# DC075B_DECOUPLING.net
KiCad netlist of a schematic drawn in Altium Designer
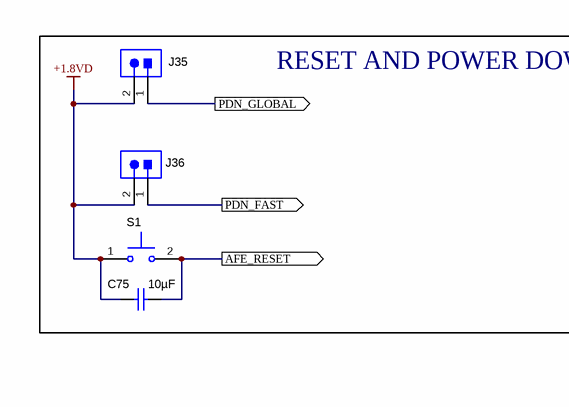
[diagram p0: DC075B_DECOUPLING.SchDoc, top left]
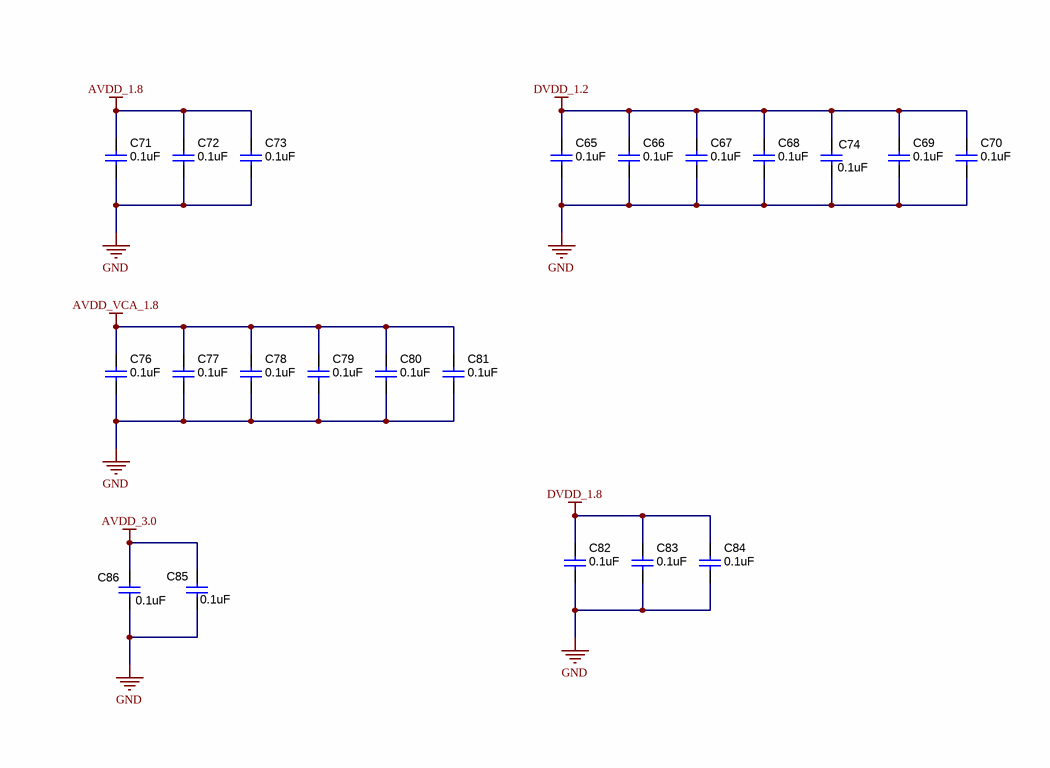
[diagram p1: DC075B_DECOUPLING.SchDoc, top right]
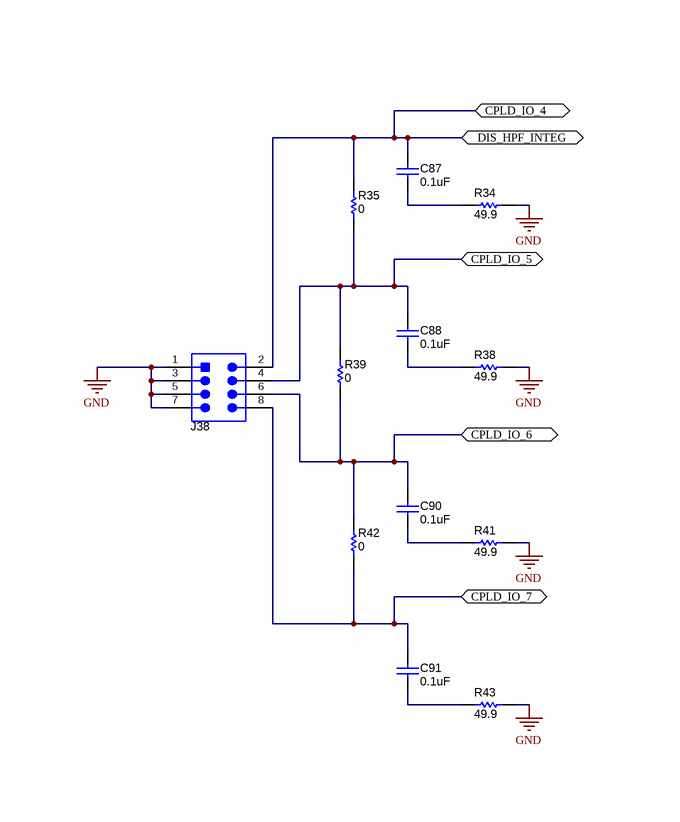
[diagram p2: DC075B_DECOUPLING.SchDoc, bottom left]
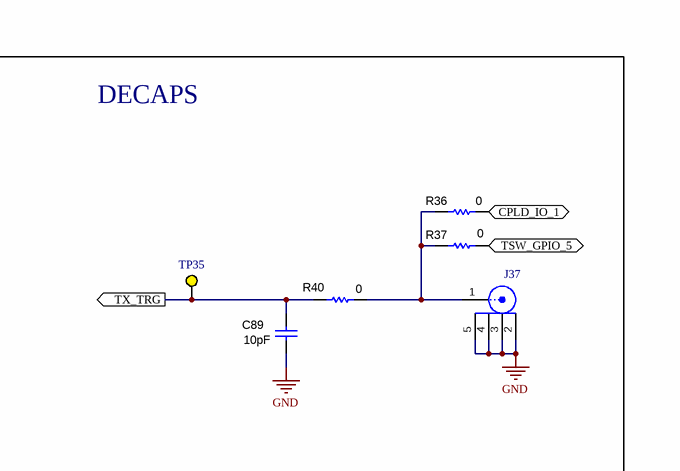
[diagram p3: DC075B_DECOUPLING.SchDoc, bottom right]

(export (version "E")
  (design (tool "Eeschema 10.0.6"))
  (components
    (comp (ref "C65")
      (value "0.1uF")
      (footprint "0402")
      (description "CAP, CERM, 0.1 uF, 16 V, +/- 10%, X7R, 0402")
      (fields
        (field (name "PARTNUMBER") "GRM155R71C104KA88D")
        (field (name "MANUFACTURER") "MuRata")
        (field (name "PUBLISHER") "Texas Instruments")
      )
      (libsource (lib "Altium Vault - TI") (part "Capacitor"))
    )
    (comp (ref "C66")
      (value "0.1uF")
      (footprint "0402")
      (description "CAP, CERM, 0.1 uF, 16 V, +/- 10%, X7R, 0402")
      (fields
        (field (name "PARTNUMBER") "GRM155R71C104KA88D")
        (field (name "MANUFACTURER") "MuRata")
        (field (name "PUBLISHER") "Texas Instruments")
      )
      (libsource (lib "Altium Vault - TI") (part "Capacitor"))
    )
    (comp (ref "C67")
      (value "0.1uF")
      (footprint "0402")
      (description "CAP, CERM, 0.1 uF, 16 V, +/- 10%, X7R, 0402")
      (fields
        (field (name "PARTNUMBER") "GRM155R71C104KA88D")
        (field (name "MANUFACTURER") "MuRata")
        (field (name "PUBLISHER") "Texas Instruments")
      )
      (libsource (lib "Altium Vault - TI") (part "Capacitor"))
    )
    (comp (ref "C68")
      (value "0.1uF")
      (footprint "0402")
      (description "CAP, CERM, 0.1 uF, 16 V, +/- 10%, X7R, 0402")
      (fields
        (field (name "PARTNUMBER") "GRM155R71C104KA88D")
        (field (name "MANUFACTURER") "MuRata")
        (field (name "PUBLISHER") "Texas Instruments")
      )
      (libsource (lib "Altium Vault - TI") (part "Capacitor"))
    )
    (comp (ref "C69")
      (value "0.1uF")
      (footprint "0402")
      (description "CAP, CERM, 0.1 uF, 16 V, +/- 10%, X7R, 0402")
      (fields
        (field (name "PARTNUMBER") "GRM155R71C104KA88D")
        (field (name "MANUFACTURER") "MuRata")
        (field (name "PUBLISHER") "Texas Instruments")
      )
      (libsource (lib "Altium Vault - TI") (part "Capacitor"))
    )
    (comp (ref "C70")
      (value "0.1uF")
      (footprint "0402")
      (description "CAP, CERM, 0.1 uF, 16 V, +/- 10%, X7R, 0402")
      (fields
        (field (name "PARTNUMBER") "GRM155R71C104KA88D")
        (field (name "MANUFACTURER") "MuRata")
        (field (name "PUBLISHER") "Texas Instruments")
      )
      (libsource (lib "Altium Vault - TI") (part "Capacitor"))
    )
    (comp (ref "C71")
      (value "0.1uF")
      (footprint "0402")
      (description "CAP, CERM, 0.1 uF, 16 V, +/- 10%, X7R, 0402")
      (fields
        (field (name "PARTNUMBER") "GRM155R71C104KA88D")
        (field (name "MANUFACTURER") "MuRata")
        (field (name "PUBLISHER") "Texas Instruments")
      )
      (libsource (lib "Altium Vault - TI") (part "Capacitor"))
    )
    (comp (ref "C72")
      (value "0.1uF")
      (footprint "0402")
      (description "CAP, CERM, 0.1 uF, 16 V, +/- 10%, X7R, 0402")
      (fields
        (field (name "PARTNUMBER") "GRM155R71C104KA88D")
        (field (name "MANUFACTURER") "MuRata")
        (field (name "PUBLISHER") "Texas Instruments")
      )
      (libsource (lib "Altium Vault - TI") (part "Capacitor"))
    )
    (comp (ref "C73")
      (value "0.1uF")
      (footprint "0402")
      (description "CAP, CERM, 0.1 uF, 16 V, +/- 10%, X7R, 0402")
      (fields
        (field (name "PARTNUMBER") "GRM155R71C104KA88D")
        (field (name "MANUFACTURER") "MuRata")
        (field (name "PUBLISHER") "Texas Instruments")
      )
      (libsource (lib "Altium Vault - TI") (part "Capacitor"))
    )
    (comp (ref "C74")
      (value "0.1uF")
      (footprint "0402")
      (description "CAP, CERM, 0.1 uF, 16 V, +/- 10%, X7R, 0402")
      (fields
        (field (name "PARTNUMBER") "GRM155R71C104KA88D")
        (field (name "MANUFACTURER") "MuRata")
        (field (name "PUBLISHER") "Texas Instruments")
      )
      (libsource (lib "Altium Vault - TI") (part "Capacitor"))
    )
    (comp (ref "C75")
      (value "CC0805ZKY5V6BB106")
      (footprint "0805_HV")
      (description "CAP, CERM, 10 µF, 10 V,+80/-20%, Y5V, 0805")
      (fields (field (name "VALUEDISPLAYED") "10µF") (field (name "MANUFACTURER") "Yageo"))
      (libsource (lib "Altium Vault - TI") (part "CMP-0085574-1"))
    )
    (comp (ref "C76")
      (value "0.1uF")
      (footprint "0402")
      (description "CAP, CERM, 0.1 uF, 16 V, +/- 10%, X7R, 0402")
      (fields
        (field (name "PARTNUMBER") "GRM155R71C104KA88D")
        (field (name "MANUFACTURER") "MuRata")
        (field (name "PUBLISHER") "Texas Instruments")
      )
      (libsource (lib "Altium Vault - TI") (part "Capacitor"))
    )
    (comp (ref "C77")
      (value "0.1uF")
      (footprint "0402")
      (description "CAP, CERM, 0.1 uF, 16 V, +/- 10%, X7R, 0402")
      (fields
        (field (name "PARTNUMBER") "GRM155R71C104KA88D")
        (field (name "MANUFACTURER") "MuRata")
        (field (name "PUBLISHER") "Texas Instruments")
      )
      (libsource (lib "Altium Vault - TI") (part "Capacitor"))
    )
    (comp (ref "C78")
      (value "0.1uF")
      (footprint "0402")
      (description "CAP, CERM, 0.1 uF, 16 V, +/- 10%, X7R, 0402")
      (fields
        (field (name "PARTNUMBER") "GRM155R71C104KA88D")
        (field (name "MANUFACTURER") "MuRata")
        (field (name "PUBLISHER") "Texas Instruments")
      )
      (libsource (lib "Altium Vault - TI") (part "Capacitor"))
    )
    (comp (ref "C79")
      (value "0.1uF")
      (footprint "0402")
      (description "CAP, CERM, 0.1 uF, 16 V, +/- 10%, X7R, 0402")
      (fields
        (field (name "PARTNUMBER") "GRM155R71C104KA88D")
        (field (name "MANUFACTURER") "MuRata")
        (field (name "PUBLISHER") "Texas Instruments")
      )
      (libsource (lib "Altium Vault - TI") (part "Capacitor"))
    )
    (comp (ref "C80")
      (value "0.1uF")
      (footprint "0402")
      (description "CAP, CERM, 0.1 uF, 16 V, +/- 10%, X7R, 0402")
      (fields
        (field (name "PARTNUMBER") "GRM155R71C104KA88D")
        (field (name "MANUFACTURER") "MuRata")
        (field (name "PUBLISHER") "Texas Instruments")
      )
      (libsource (lib "Altium Vault - TI") (part "Capacitor"))
    )
    (comp (ref "C81")
      (value "0.1uF")
      (footprint "0402")
      (description "CAP, CERM, 0.1 uF, 16 V, +/- 10%, X7R, 0402")
      (fields
        (field (name "PARTNUMBER") "GRM155R71C104KA88D")
        (field (name "MANUFACTURER") "MuRata")
        (field (name "PUBLISHER") "Texas Instruments")
      )
      (libsource (lib "Altium Vault - TI") (part "Capacitor"))
    )
    (comp (ref "C82")
      (value "0.1uF")
      (footprint "0402")
      (description "CAP, CERM, 0.1 uF, 16 V, +/- 10%, X7R, 0402")
      (fields
        (field (name "PARTNUMBER") "GRM155R71C104KA88D")
        (field (name "MANUFACTURER") "MuRata")
        (field (name "PUBLISHER") "Texas Instruments")
      )
      (libsource (lib "Altium Vault - TI") (part "Capacitor"))
    )
    (comp (ref "C83")
      (value "0.1uF")
      (footprint "0402")
      (description "CAP, CERM, 0.1 uF, 16 V, +/- 10%, X7R, 0402")
      (fields
        (field (name "PARTNUMBER") "GRM155R71C104KA88D")
        (field (name "MANUFACTURER") "MuRata")
        (field (name "PUBLISHER") "Texas Instruments")
      )
      (libsource (lib "Altium Vault - TI") (part "Capacitor"))
    )
    (comp (ref "C84")
      (value "0.1uF")
      (footprint "0402")
      (description "CAP, CERM, 0.1 uF, 16 V, +/- 10%, X7R, 0402")
      (fields
        (field (name "PARTNUMBER") "GRM155R71C104KA88D")
        (field (name "MANUFACTURER") "MuRata")
        (field (name "PUBLISHER") "Texas Instruments")
      )
      (libsource (lib "Altium Vault - TI") (part "Capacitor"))
    )
    (comp (ref "C85")
      (value "0.1uF")
      (footprint "0402")
      (description "CAP, CERM, 0.1 uF, 16 V, +/- 10%, X7R, 0402")
      (fields
        (field (name "PARTNUMBER") "GRM155R71C104KA88D")
        (field (name "MANUFACTURER") "MuRata")
        (field (name "PUBLISHER") "Texas Instruments")
      )
      (libsource (lib "Altium Vault - TI") (part "Capacitor"))
    )
    (comp (ref "C86")
      (value "0.1uF")
      (footprint "0402")
      (description "CAP, CERM, 0.1 uF, 16 V, +/- 10%, X7R, 0402")
      (fields
        (field (name "PARTNUMBER") "GRM155R71C104KA88D")
        (field (name "MANUFACTURER") "MuRata")
        (field (name "PUBLISHER") "Texas Instruments")
      )
      (libsource (lib "Altium Vault - TI") (part "Capacitor"))
    )
    (comp (ref "C87")
      (value "0.1uF")
      (footprint "0402")
      (description "CAP, CERM, 0.1 uF, 16 V, +/- 10%, X7R, 0402")
      (fields
        (field (name "PARTNUMBER") "GRM155R71C104KA88D")
        (field (name "MANUFACTURER") "MuRata")
        (field (name "PUBLISHER") "Texas Instruments")
      )
      (libsource (lib "Altium Vault - TI") (part "Capacitor"))
    )
    (comp (ref "C88")
      (value "0.1uF")
      (footprint "0402")
      (description "CAP, CERM, 0.1 uF, 16 V, +/- 10%, X7R, 0402")
      (fields
        (field (name "PARTNUMBER") "GRM155R71C104KA88D")
        (field (name "MANUFACTURER") "MuRata")
        (field (name "PUBLISHER") "Texas Instruments")
      )
      (libsource (lib "Altium Vault - TI") (part "Capacitor"))
    )
    (comp (ref "C89")
      (value "10pF")
      (footprint "0402")
      (description "CAP, CERM, 10 pF, 50 V, +/- 5%, C0G/NP0, 0402")
      (fields
        (field (name "PARTNUMBER") "GRM1555C1H100JA01D")
        (field (name "MANUFACTURER") "MuRata")
        (field (name "PUBLISHER") "Texas Instruments")
      )
      (libsource (lib "Altium Vault - TI") (part "Capacitor"))
    )
    (comp (ref "C90")
      (value "0.1uF")
      (footprint "0402")
      (description "CAP, CERM, 0.1 uF, 16 V, +/- 10%, X7R, 0402")
      (fields
        (field (name "PARTNUMBER") "GRM155R71C104KA88D")
        (field (name "MANUFACTURER") "MuRata")
        (field (name "PUBLISHER") "Texas Instruments")
      )
      (libsource (lib "Altium Vault - TI") (part "Capacitor"))
    )
    (comp (ref "C91")
      (value "0.1uF")
      (footprint "0402")
      (description "CAP, CERM, 0.1 uF, 16 V, +/- 10%, X7R, 0402")
      (fields
        (field (name "PARTNUMBER") "GRM155R71C104KA88D")
        (field (name "MANUFACTURER") "MuRata")
        (field (name "PUBLISHER") "Texas Instruments")
      )
      (libsource (lib "Altium Vault - TI") (part "Capacitor"))
    )
    (comp (ref "J35")
      (value "Header_2x1")
      (footprint "TSW-102-07-G-S")
      (description "Header, 100mil, 2x1, Gold, TH")
      (fields (field (name "PARTNUMBER") "TSW-102-07-G-S") (field (name "MANUFACTURER") "Samtec"))
      (libsource (lib "Altium Vault - TI") (part "Header_2x1"))
    )
    (comp (ref "J36")
      (value "Header_2x1")
      (footprint "TSW-102-07-G-S")
      (description "Header, 100mil, 2x1, Gold, TH")
      (fields (field (name "PARTNUMBER") "TSW-102-07-G-S") (field (name "MANUFACTURER") "Samtec"))
      (libsource (lib "Altium Vault - TI") (part "Header_2x1"))
    )
    (comp (ref "J37")
      (value "5-1814832-1")
      (footprint "TE_5-1814832-1")
      (description "SMA Straight PCB Socket Die Cast, 50 Ohm, TH")
      (fields (field (name "MANUFACTURER") "TE Connectivity") (field (name "PUBLISHER") "Texas Instruments"))
      (libsource (lib "Altium Vault - TI") (part "SMA_Contact1_GND2345"))
    )
    (comp (ref "J38")
      (value "Header_4x2")
      (footprint "TSW-104-07-G-D")
      (description "Header, 100mil, 4x2, Gold, TH")
      (fields (field (name "PARTNUMBER") "TSW-104-07-G-D") (field (name "MANUFACTURER") "Samtec"))
      (libsource (lib "Altium Vault - TI") (part "Header_4x2"))
    )
    (comp (ref "R34")
      (value "Resistor")
      (footprint "0402")
      (description "RES, 49.9, 1%, 0.063 W, AEC-Q200 Grade 0, 0402")
      (fields
        (field (name "MANUFACTURER") "Vishay-Dale")
        (field (name "PARTNUMBER") "CRCW040249R9FKED")
        (field (name "VALUEDISPLAYED") "49.9")
      )
      (libsource (lib "Altium Vault - TI") (part "Resistor"))
    )
    (comp (ref "R35")
      (value "0")
      (footprint "0402")
      (description "RES, 0, 5%, 0.063 W, AEC-Q200 Grade 0, 0402")
      (fields (field (name "MANUFACTURER") "Vishay-Dale") (field (name "PARTNUMBER") "CRCW04020000Z0ED"))
      (libsource (lib "Altium Vault - TI") (part "Resistor"))
    )
    (comp (ref "R36")
      (value "0")
      (footprint "0402")
      (description "RES, 0, 5%, 0.063 W, AEC-Q200 Grade 0, 0402")
      (fields (field (name "MANUFACTURER") "Vishay-Dale") (field (name "PARTNUMBER") "CRCW04020000Z0ED"))
      (libsource (lib "Altium Vault - TI") (part "Resistor"))
    )
    (comp (ref "R37")
      (value "0")
      (footprint "0402")
      (description "RES, 0, 5%, 0.063 W, AEC-Q200 Grade 0, 0402")
      (fields (field (name "MANUFACTURER") "Vishay-Dale") (field (name "PARTNUMBER") "CRCW04020000Z0ED"))
      (libsource (lib "Altium Vault - TI") (part "Resistor"))
    )
    (comp (ref "R38")
      (value "Resistor")
      (footprint "0402")
      (description "RES, 49.9, 1%, 0.063 W, AEC-Q200 Grade 0, 0402")
      (fields
        (field (name "MANUFACTURER") "Vishay-Dale")
        (field (name "PARTNUMBER") "CRCW040249R9FKED")
        (field (name "VALUEDISPLAYED") "49.9")
      )
      (libsource (lib "Altium Vault - TI") (part "Resistor"))
    )
    (comp (ref "R39")
      (value "0")
      (footprint "0402")
      (description "RES, 0, 5%, 0.063 W, AEC-Q200 Grade 0, 0402")
      (fields (field (name "MANUFACTURER") "Vishay-Dale") (field (name "PARTNUMBER") "CRCW04020000Z0ED"))
      (libsource (lib "Altium Vault - TI") (part "Resistor"))
    )
    (comp (ref "R40")
      (value "0")
      (footprint "0402")
      (description "RES, 0, 5%, 0.063 W, AEC-Q200 Grade 0, 0402")
      (fields (field (name "MANUFACTURER") "Vishay-Dale") (field (name "PARTNUMBER") "CRCW04020000Z0ED"))
      (libsource (lib "Altium Vault - TI") (part "Resistor"))
    )
    (comp (ref "R41")
      (value "Resistor")
      (footprint "0402")
      (description "RES, 49.9, 1%, 0.063 W, AEC-Q200 Grade 0, 0402")
      (fields
        (field (name "MANUFACTURER") "Vishay-Dale")
        (field (name "PARTNUMBER") "CRCW040249R9FKED")
        (field (name "VALUEDISPLAYED") "49.9")
      )
      (libsource (lib "Altium Vault - TI") (part "Resistor"))
    )
    (comp (ref "R42")
      (value "0")
      (footprint "0402")
      (description "RES, 0, 5%, 0.063 W, AEC-Q200 Grade 0, 0402")
      (fields (field (name "MANUFACTURER") "Vishay-Dale") (field (name "PARTNUMBER") "CRCW04020000Z0ED"))
      (libsource (lib "Altium Vault - TI") (part "Resistor"))
    )
    (comp (ref "R43")
      (value "Resistor")
      (footprint "0402")
      (description "RES, 49.9, 1%, 0.063 W, AEC-Q200 Grade 0, 0402")
      (fields
        (field (name "MANUFACTURER") "Vishay-Dale")
        (field (name "PARTNUMBER") "CRCW040249R9FKED")
        (field (name "VALUEDISPLAYED") "49.9")
      )
      (libsource (lib "Altium Vault - TI") (part "Resistor"))
    )
    (comp (ref "S1")
      (value "SKRKAEE020")
      (footprint "SW_SKRKAE")
      (description "Switch, SPST-NO, 0.05 A, 12 VDC, SMT")
      (fields (field (name "MANUFACTURER") "Alps") (field (name "PUBLISHER") "Texas Instruments"))
      (libsource (lib "Altium Vault - TI") (part "Switch_PushButton"))
    )
    (comp (ref "TP35")
      (value "5004")
      (footprint "Keystone5004")
      (description "Test Point, Miniature, Yellow, TH")
      (fields (field (name "MANUFACTURER") "Keystone") (field (name "PUBLISHER") "Texas Instruments"))
      (libsource (lib "Altium Vault - TI") (part "5004"))
    )
  )
  (nets
    (net (code "1") (name "+1.8VD") (class "Default")
      (node (ref "C75") (pin "1") (pinfunction "1_1") (pintype "passive"))
      (node (ref "J35") (pin "2") (pinfunction "2_2") (pintype "passive"))
      (node (ref "J36") (pin "2") (pinfunction "2_2") (pintype "passive"))
      (node (ref "S1") (pin "1") (pinfunction "1_1") (pintype "passive"))
    )
    (net (code "2") (name "/AFE_RESET") (class "Default")
      (node (ref "C75") (pin "2") (pinfunction "2_2") (pintype "passive"))
      (node (ref "S1") (pin "2") (pinfunction "2_2") (pintype "passive"))
    )
    (net (code "3") (name "/CPLD_IO_1") (class "Default")
      (node (ref "R36") (pin "1") (pinfunction "1_1") (pintype "passive"))
    )
    (net (code "4") (name "/CPLD_IO_4") (class "Default")
      (node (ref "C87") (pin "1") (pinfunction "1_1") (pintype "passive"))
      (node (ref "J38") (pin "2") (pinfunction "2_2") (pintype "passive"))
      (node (ref "R35") (pin "2") (pinfunction "2_2") (pintype "passive"))
    )
    (net (code "5") (name "/CPLD_IO_5") (class "Default")
      (node (ref "C88") (pin "1") (pinfunction "1_1") (pintype "passive"))
      (node (ref "J38") (pin "4") (pinfunction "4_4") (pintype "passive"))
      (node (ref "R35") (pin "1") (pinfunction "1_1") (pintype "passive"))
      (node (ref "R39") (pin "2") (pinfunction "2_2") (pintype "passive"))
    )
    (net (code "6") (name "/CPLD_IO_6") (class "Default")
      (node (ref "C90") (pin "1") (pinfunction "1_1") (pintype "passive"))
      (node (ref "J38") (pin "6") (pinfunction "6_6") (pintype "passive"))
      (node (ref "R39") (pin "1") (pinfunction "1_1") (pintype "passive"))
      (node (ref "R42") (pin "2") (pinfunction "2_2") (pintype "passive"))
    )
    (net (code "7") (name "/CPLD_IO_7") (class "Default")
      (node (ref "C91") (pin "1") (pinfunction "1_1") (pintype "passive"))
      (node (ref "J38") (pin "8") (pinfunction "8_8") (pintype "passive"))
      (node (ref "R42") (pin "1") (pinfunction "1_1") (pintype "passive"))
    )
    (net (code "8") (name "/PDN_FAST") (class "Default")
      (node (ref "J36") (pin "1") (pinfunction "1_1") (pintype "passive"))
    )
    (net (code "9") (name "/PDN_GLOBAL") (class "Default")
      (node (ref "J35") (pin "1") (pinfunction "1_1") (pintype "passive"))
    )
    (net (code "10") (name "/TSW_GPIO_5") (class "Default")
      (node (ref "R37") (pin "1") (pinfunction "1_1") (pintype "passive"))
    )
    (net (code "11") (name "/TX_TRG") (class "Default")
      (node (ref "C89") (pin "2") (pinfunction "2_2") (pintype "passive"))
      (node (ref "R40") (pin "2") (pinfunction "2_2") (pintype "passive"))
      (node (ref "TP35") (pin "1") (pintype "passive"))
    )
    (net (code "12") (name "AVDD_1.8") (class "Default")
      (node (ref "C71") (pin "1") (pinfunction "1_1") (pintype "passive"))
      (node (ref "C72") (pin "1") (pinfunction "1_1") (pintype "passive"))
      (node (ref "C73") (pin "1") (pinfunction "1_1") (pintype "passive"))
    )
    (net (code "13") (name "AVDD_3.0") (class "Default")
      (node (ref "C85") (pin "1") (pinfunction "1_1") (pintype "passive"))
      (node (ref "C86") (pin "1") (pinfunction "1_1") (pintype "passive"))
    )
    (net (code "14") (name "AVDD_VCA_1.8") (class "Default")
      (node (ref "C76") (pin "1") (pinfunction "1_1") (pintype "passive"))
      (node (ref "C77") (pin "1") (pinfunction "1_1") (pintype "passive"))
      (node (ref "C78") (pin "1") (pinfunction "1_1") (pintype "passive"))
      (node (ref "C79") (pin "1") (pinfunction "1_1") (pintype "passive"))
      (node (ref "C80") (pin "1") (pinfunction "1_1") (pintype "passive"))
      (node (ref "C81") (pin "1") (pinfunction "1_1") (pintype "passive"))
    )
    (net (code "15") (name "DVDD_1.2") (class "Default")
      (node (ref "C65") (pin "1") (pinfunction "1_1") (pintype "passive"))
      (node (ref "C66") (pin "1") (pinfunction "1_1") (pintype "passive"))
      (node (ref "C67") (pin "1") (pinfunction "1_1") (pintype "passive"))
      (node (ref "C68") (pin "1") (pinfunction "1_1") (pintype "passive"))
      (node (ref "C69") (pin "1") (pinfunction "1_1") (pintype "passive"))
      (node (ref "C70") (pin "1") (pinfunction "1_1") (pintype "passive"))
      (node (ref "C74") (pin "1") (pinfunction "1_1") (pintype "passive"))
    )
    (net (code "16") (name "DVDD_1.8") (class "Default")
      (node (ref "C82") (pin "1") (pinfunction "1_1") (pintype "passive"))
      (node (ref "C83") (pin "1") (pinfunction "1_1") (pintype "passive"))
      (node (ref "C84") (pin "1") (pinfunction "1_1") (pintype "passive"))
    )
    (net (code "17") (name "GND") (class "Default")
      (node (ref "C65") (pin "2") (pinfunction "2_2") (pintype "passive"))
      (node (ref "C66") (pin "2") (pinfunction "2_2") (pintype "passive"))
      (node (ref "C67") (pin "2") (pinfunction "2_2") (pintype "passive"))
      (node (ref "C68") (pin "2") (pinfunction "2_2") (pintype "passive"))
      (node (ref "C69") (pin "2") (pinfunction "2_2") (pintype "passive"))
      (node (ref "C70") (pin "2") (pinfunction "2_2") (pintype "passive"))
      (node (ref "C71") (pin "2") (pinfunction "2_2") (pintype "passive"))
      (node (ref "C72") (pin "2") (pinfunction "2_2") (pintype "passive"))
      (node (ref "C73") (pin "2") (pinfunction "2_2") (pintype "passive"))
      (node (ref "C74") (pin "2") (pinfunction "2_2") (pintype "passive"))
      (node (ref "C76") (pin "2") (pinfunction "2_2") (pintype "passive"))
      (node (ref "C77") (pin "2") (pinfunction "2_2") (pintype "passive"))
      (node (ref "C78") (pin "2") (pinfunction "2_2") (pintype "passive"))
      (node (ref "C79") (pin "2") (pinfunction "2_2") (pintype "passive"))
      (node (ref "C80") (pin "2") (pinfunction "2_2") (pintype "passive"))
      (node (ref "C81") (pin "2") (pinfunction "2_2") (pintype "passive"))
      (node (ref "C82") (pin "2") (pinfunction "2_2") (pintype "passive"))
      (node (ref "C83") (pin "2") (pinfunction "2_2") (pintype "passive"))
      (node (ref "C84") (pin "2") (pinfunction "2_2") (pintype "passive"))
      (node (ref "C85") (pin "2") (pinfunction "2_2") (pintype "passive"))
      (node (ref "C86") (pin "2") (pinfunction "2_2") (pintype "passive"))
      (node (ref "C89") (pin "1") (pinfunction "1_1") (pintype "passive"))
      (node (ref "J37") (pin "2") (pinfunction "2_2") (pintype "passive"))
      (node (ref "J37") (pin "3") (pinfunction "3_3") (pintype "passive"))
      (node (ref "J37") (pin "4") (pinfunction "4_4") (pintype "passive"))
      (node (ref "J37") (pin "5") (pinfunction "5_5") (pintype "passive"))
      (node (ref "J38") (pin "1") (pinfunction "1_1") (pintype "passive"))
      (node (ref "J38") (pin "3") (pinfunction "3_3") (pintype "passive"))
      (node (ref "J38") (pin "5") (pinfunction "5_5") (pintype "passive"))
      (node (ref "J38") (pin "7") (pinfunction "7_7") (pintype "passive"))
      (node (ref "R34") (pin "1") (pinfunction "1_1") (pintype "passive"))
      (node (ref "R38") (pin "1") (pinfunction "1_1") (pintype "passive"))
      (node (ref "R41") (pin "1") (pinfunction "1_1") (pintype "passive"))
      (node (ref "R43") (pin "1") (pinfunction "1_1") (pintype "passive"))
    )
    (net (code "18") (name "Net-(C87-Pad2)") (class "Default")
      (node (ref "C87") (pin "2") (pinfunction "2_2") (pintype "passive"))
      (node (ref "R34") (pin "2") (pinfunction "2_2") (pintype "passive"))
    )
    (net (code "19") (name "Net-(C88-Pad2)") (class "Default")
      (node (ref "C88") (pin "2") (pinfunction "2_2") (pintype "passive"))
      (node (ref "R38") (pin "2") (pinfunction "2_2") (pintype "passive"))
    )
    (net (code "20") (name "Net-(C90-Pad2)") (class "Default")
      (node (ref "C90") (pin "2") (pinfunction "2_2") (pintype "passive"))
      (node (ref "R41") (pin "2") (pinfunction "2_2") (pintype "passive"))
    )
    (net (code "21") (name "Net-(C91-Pad2)") (class "Default")
      (node (ref "C91") (pin "2") (pinfunction "2_2") (pintype "passive"))
      (node (ref "R43") (pin "2") (pinfunction "2_2") (pintype "passive"))
    )
    (net (code "22") (name "Net-(J37-Pad1)") (class "Default")
      (node (ref "J37") (pin "1") (pinfunction "1_1") (pintype "passive"))
      (node (ref "R36") (pin "2") (pinfunction "2_2") (pintype "passive"))
      (node (ref "R37") (pin "2") (pinfunction "2_2") (pintype "passive"))
      (node (ref "R40") (pin "1") (pinfunction "1_1") (pintype "passive"))
    )
  )
)
